# GregTrack_BIG_POW_v1_0.net
KiCad netlist of a schematic drawn in Altium Designer
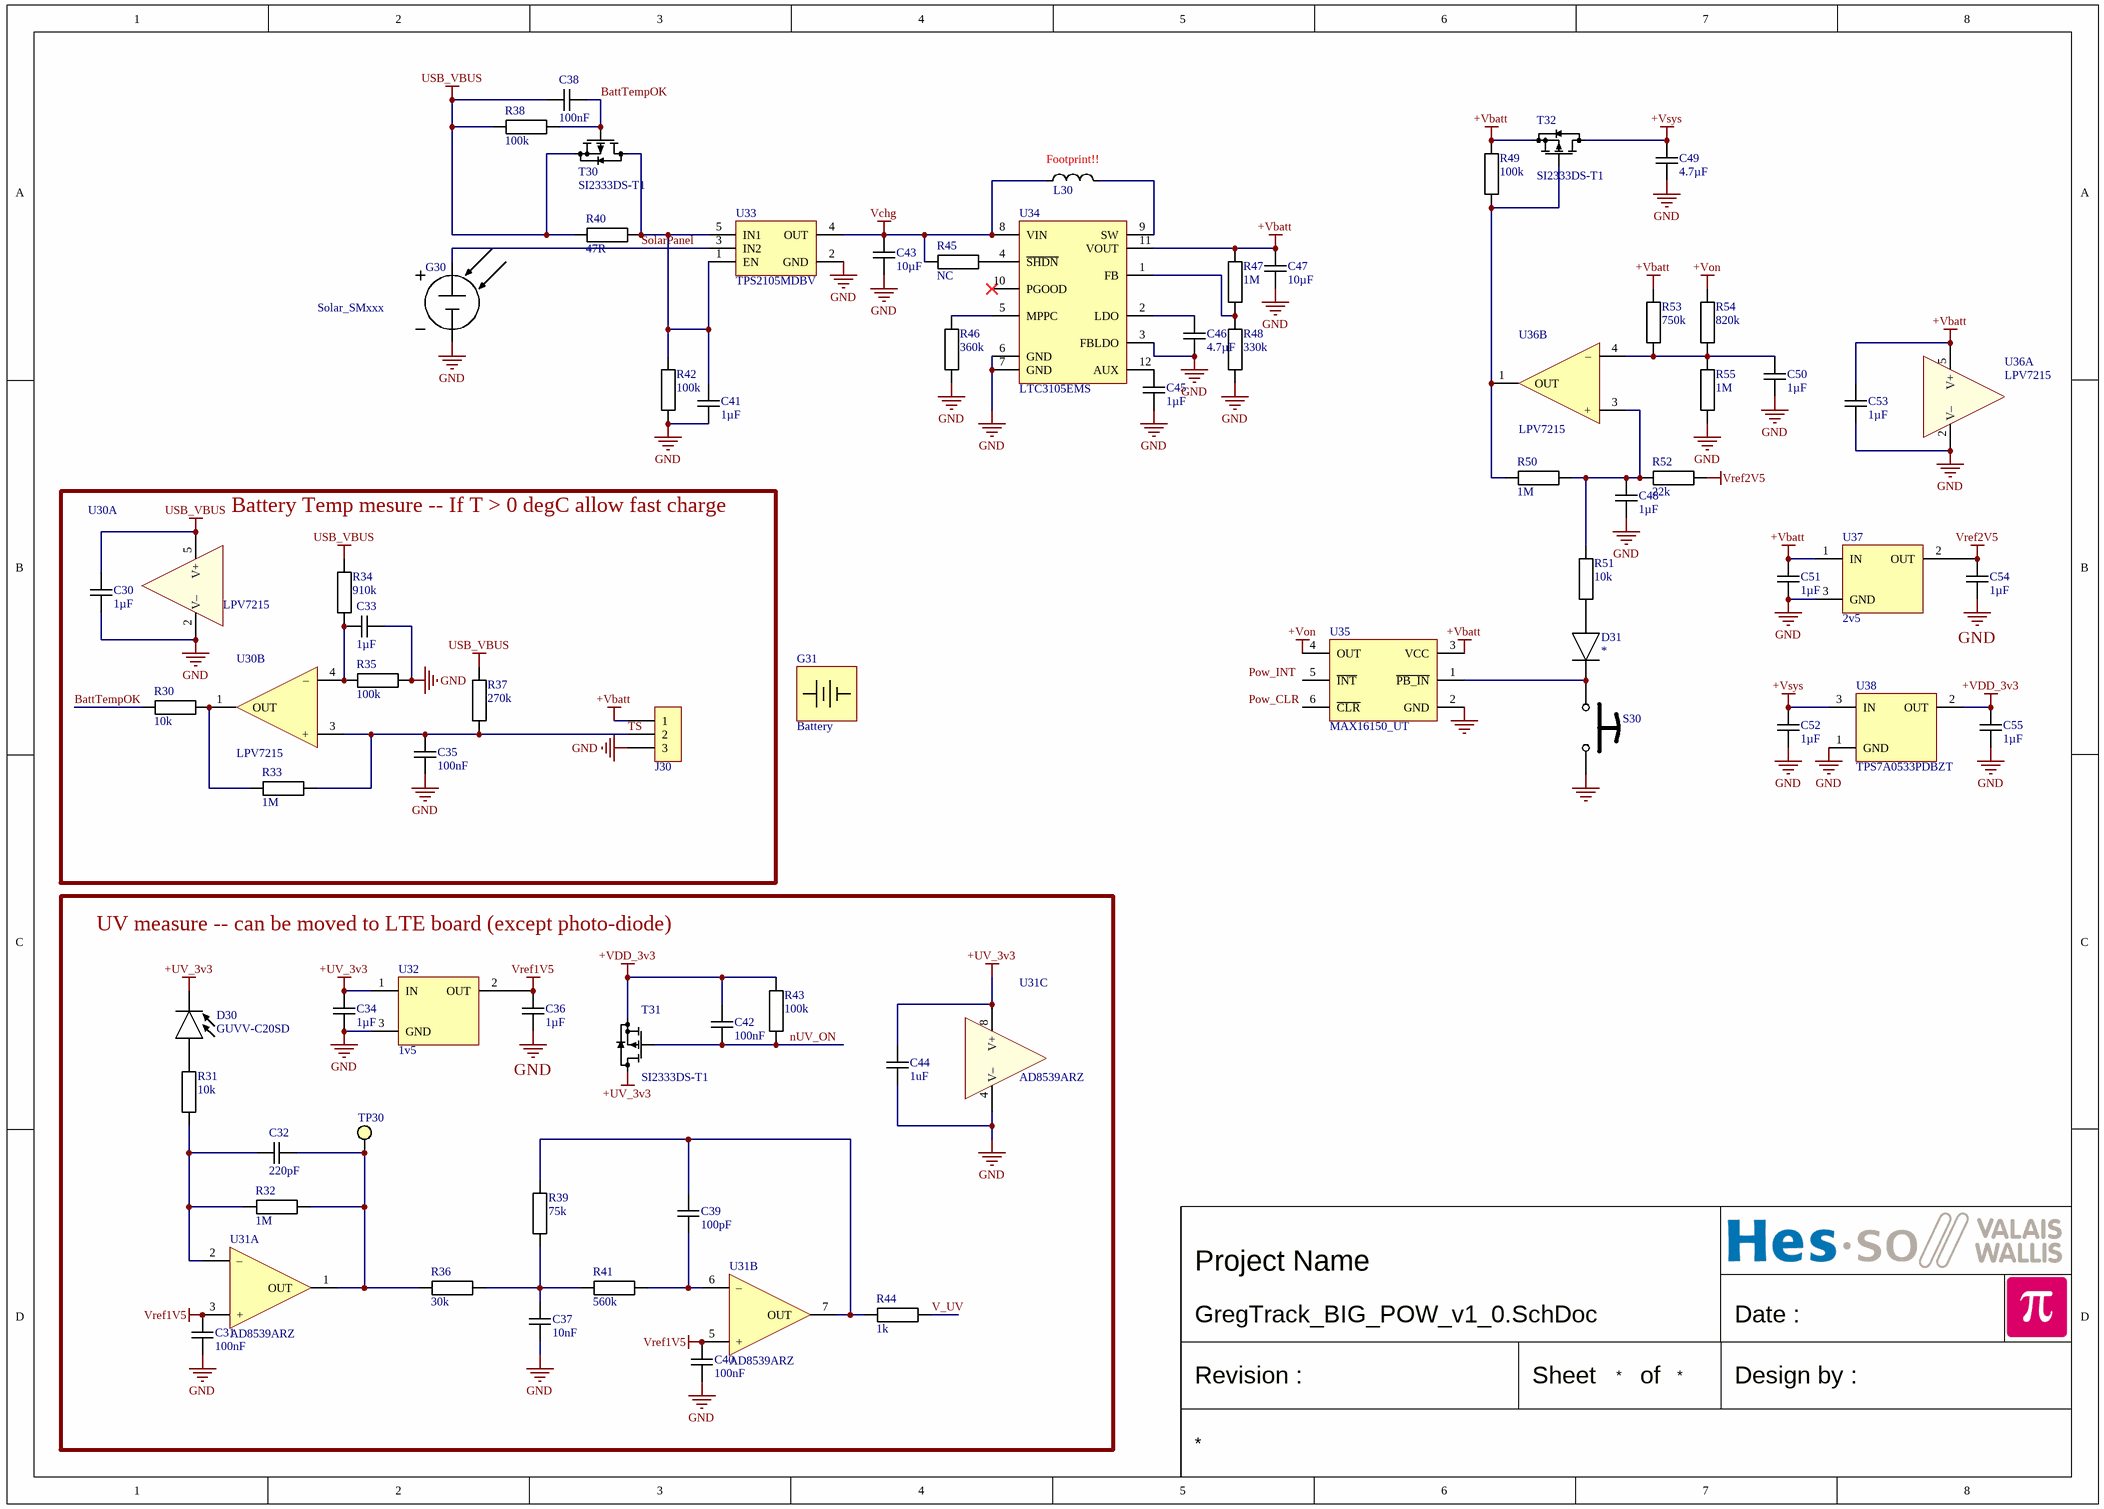
[diagram p0: GregTrack_BIG_POW_v1_0.SchDoc]

(export (version "E")
  (design (tool "Eeschema 10.0.6"))
  (components
    (comp (ref "C30")
      (value "1µF")
      (footprint "CAPACITOR 1005 REFLOW")
      (description "Capacitor 1005")
      (fields (field (name "TOLERANCE") "+/-20%") (field (name "VOLTAGE") "10V"))
      (libsource (lib "Capacitor") (part "Capacitor"))
    )
    (comp (ref "C31")
      (value "100nF")
      (footprint "CAPACITOR 1005 REFLOW")
      (description "Capacitor 1005")
      (fields (field (name "TOLERANCE") "+/-20%") (field (name "VOLTAGE") "10V"))
      (libsource (lib "Capacitor") (part "Capacitor"))
    )
    (comp (ref "C32")
      (value "220pF")
      (footprint "CAPACITOR 1005 REFLOW")
      (description "Capacitor 1005")
      (fields (field (name "TOLERANCE") "+/-5%") (field (name "VOLTAGE") "10V"))
      (libsource (lib "Capacitor") (part "Capacitor"))
    )
    (comp (ref "C33")
      (value "1µF")
      (footprint "CAPACITOR 1005 REFLOW")
      (description "Capacitor 1005")
      (fields (field (name "TOLERANCE") "+/-20%") (field (name "VOLTAGE") "10V"))
      (libsource (lib "Capacitor") (part "Capacitor"))
    )
    (comp (ref "C34")
      (value "1µF")
      (footprint "CAPACITOR 1005 REFLOW")
      (description "Capacitor 1005")
      (fields (field (name "TOLERANCE") "+/-20%") (field (name "VOLTAGE") "10V"))
      (libsource (lib "Capacitor") (part "Capacitor"))
    )
    (comp (ref "C35")
      (value "100nF")
      (footprint "CAPACITOR 1005 REFLOW")
      (description "Capacitor 1005")
      (fields (field (name "TOLERANCE") "+/-20%") (field (name "VOLTAGE") "10V"))
      (libsource (lib "Capacitor") (part "Capacitor"))
    )
    (comp (ref "C36")
      (value "1µF")
      (footprint "CAPACITOR 1005 REFLOW")
      (description "Capacitor 1005")
      (fields (field (name "TOLERANCE") "+/-20%") (field (name "VOLTAGE") "10V"))
      (libsource (lib "Capacitor") (part "Capacitor"))
    )
    (comp (ref "C37")
      (value "10nF")
      (footprint "CAPACITOR 1005 REFLOW")
      (description "Capacitor 1005")
      (fields (field (name "TOLERANCE") "+/-5%") (field (name "VOLTAGE") "10V"))
      (libsource (lib "Capacitor") (part "Capacitor"))
    )
    (comp (ref "C38")
      (value "100nF")
      (footprint "CAPACITOR 2012 REFLOW")
      (description "Capacitor 2012")
      (fields (field (name "TOLERANCE") "+/-20%") (field (name "VOLTAGE") "10V"))
      (libsource (lib "Capacitor") (part "Capacitor"))
    )
    (comp (ref "C39")
      (value "100pF")
      (footprint "CAPACITOR 1005 REFLOW")
      (description "Capacitor 1005")
      (fields (field (name "TOLERANCE") "+/-5%") (field (name "VOLTAGE") "10V"))
      (libsource (lib "Capacitor") (part "Capacitor"))
    )
    (comp (ref "C40")
      (value "100nF")
      (footprint "CAPACITOR 1005 REFLOW")
      (description "Capacitor 1005")
      (fields (field (name "TOLERANCE") "+/-20%") (field (name "VOLTAGE") "10V"))
      (libsource (lib "Capacitor") (part "Capacitor"))
    )
    (comp (ref "C41")
      (value "1µF")
      (footprint "CAPACITOR 2012 REFLOW")
      (description "Capacitor 2012")
      (fields (field (name "TOLERANCE") "+/-20%") (field (name "VOLTAGE") "10V"))
      (libsource (lib "Capacitor") (part "Capacitor"))
    )
    (comp (ref "C42")
      (value "100nF")
      (footprint "CAPACITOR 1005 REFLOW")
      (description "Capacitor 1005")
      (fields (field (name "TOLERANCE") "+/-20%") (field (name "VOLTAGE") "10V"))
      (libsource (lib "Capacitor") (part "Capacitor"))
    )
    (comp (ref "C43")
      (value "10µF")
      (footprint "CAPACITOR 2012 REFLOW")
      (description "Capacitor 2012")
      (fields (field (name "TOLERANCE") "+/-20%") (field (name "VOLTAGE") "10V"))
      (libsource (lib "Capacitor") (part "Capacitor"))
    )
    (comp (ref "C44")
      (value "1uF")
      (footprint "CAPACITOR 1005 REFLOW")
      (description "Capacitor 1005")
      (fields (field (name "TOLERANCE") "+/-20%") (field (name "VOLTAGE") "10V"))
      (libsource (lib "Capacitor") (part "Capacitor"))
    )
    (comp (ref "C45")
      (value "1µF")
      (footprint "CAPACITOR 1005 REFLOW")
      (description "Capacitor 1005")
      (fields (field (name "TOLERANCE") "+/-20%") (field (name "VOLTAGE") "10V"))
      (libsource (lib "Capacitor") (part "Capacitor"))
    )
    (comp (ref "C46")
      (value "4.7µF")
      (footprint "CAPACITOR 1005 REFLOW")
      (description "Capacitor 1005")
      (fields (field (name "TOLERANCE") "+/-20%") (field (name "VOLTAGE") "10V"))
      (libsource (lib "Capacitor") (part "Capacitor"))
    )
    (comp (ref "C47")
      (value "10µF")
      (footprint "CAPACITOR 2012 REFLOW")
      (description "Capacitor 2012")
      (fields (field (name "TOLERANCE") "+/-20%") (field (name "VOLTAGE") "10V"))
      (libsource (lib "Capacitor") (part "Capacitor"))
    )
    (comp (ref "C48")
      (value "1µF")
      (footprint "CAPACITOR 1005 REFLOW")
      (description "Capacitor 1005")
      (fields (field (name "TOLERANCE") "+/-20%") (field (name "VOLTAGE") "10V"))
      (libsource (lib "Capacitor") (part "Capacitor"))
    )
    (comp (ref "C49")
      (value "4.7µF")
      (footprint "CAPACITOR 1005 REFLOW")
      (description "Capacitor 1005")
      (fields (field (name "TOLERANCE") "+/-20%") (field (name "VOLTAGE") "10V"))
      (libsource (lib "Capacitor") (part "Capacitor"))
    )
    (comp (ref "C50")
      (value "1µF")
      (footprint "CAPACITOR 1005 REFLOW")
      (description "Capacitor 1005")
      (fields (field (name "TOLERANCE") "+/-20%") (field (name "VOLTAGE") "10V"))
      (libsource (lib "Capacitor") (part "Capacitor"))
    )
    (comp (ref "C51")
      (value "1µF")
      (footprint "CAPACITOR 1005 REFLOW")
      (description "Capacitor 1005")
      (fields (field (name "TOLERANCE") "+/-20%") (field (name "VOLTAGE") "10V"))
      (libsource (lib "Capacitor") (part "Capacitor"))
    )
    (comp (ref "C52")
      (value "1µF")
      (footprint "CAPACITOR 1005 REFLOW")
      (description "Capacitor 1005")
      (fields (field (name "TOLERANCE") "+/-20%") (field (name "VOLTAGE") "10V"))
      (libsource (lib "Capacitor") (part "Capacitor"))
    )
    (comp (ref "C53")
      (value "1µF")
      (footprint "CAPACITOR 1005 REFLOW")
      (description "Capacitor 1005")
      (fields (field (name "TOLERANCE") "+/-20%") (field (name "VOLTAGE") "10V"))
      (libsource (lib "Capacitor") (part "Capacitor"))
    )
    (comp (ref "C54")
      (value "1µF")
      (footprint "CAPACITOR 1005 REFLOW")
      (description "Capacitor 1005")
      (fields (field (name "TOLERANCE") "+/-20%") (field (name "VOLTAGE") "10V"))
      (libsource (lib "Capacitor") (part "Capacitor"))
    )
    (comp (ref "C55")
      (value "1µF")
      (footprint "CAPACITOR 1005 REFLOW")
      (description "Capacitor 1005")
      (fields (field (name "TOLERANCE") "+/-20%") (field (name "VOLTAGE") "10V"))
      (libsource (lib "Capacitor") (part "Capacitor"))
    )
    (comp (ref "D30")
      (value "GUVV-C20SD")
      (footprint "Photodiode Genuv GUV series")
      (description "Schottky Photodiode SMD 2.4x1.8mm")
      (libsource (lib "Diode") (part "Photodiode Genuv GUVV-C20SD"))
    )
    (comp (ref "D31")
      (value "*")
      (footprint "DIODE SOD923-F REFLOW")
      (description "Diode generic 2 leads")
      (libsource (lib "Diode") (part "DIODE"))
    )
    (comp (ref "G30")
      (value "Solar_SMxxx")
      (footprint "SOLAR_SM531K08TF")
      (libsource (lib "ECSlib") (part "Solar_SMxxx"))
    )
    (comp (ref "G31")
      (value "Battery")
      (footprint "Battery_ICP543759PMT")
      (description "ICP622540PMT")
      (libsource (lib "ECSlib") (part "Battery"))
    )
    (comp (ref "J30")
      (value "NC")
      (footprint "PinHeader1x3 P2.54 A SMD")
      (description "Plug connector")
      (libsource (lib "PinHeader") (part "PinHeader1x3"))
    )
    (comp (ref "L30")
      (value "10uH")
      (footprint "INDUCTOR 5750 REFLOW")
      (description "Inductor IHLP2020BZER100M51")
      (libsource (lib "Inductor") (part "Inductor"))
    )
    (comp (ref "R30")
      (value "10k")
      (footprint "RESISTOR 1005 REFLOW")
      (description "Resistor 1005")
      (fields (field (name "TOLERANCE") "1%"))
      (libsource (lib "Resistor") (part "Resistor"))
    )
    (comp (ref "R31")
      (value "10k")
      (footprint "RESISTOR 1005 REFLOW")
      (description "Resistor 1005")
      (fields (field (name "TOLERANCE") "1%"))
      (libsource (lib "Resistor") (part "Resistor"))
    )
    (comp (ref "R32")
      (value "1M")
      (footprint "RESISTOR 1005 REFLOW")
      (description "Resistor 1005")
      (fields (field (name "TOLERANCE") "1%"))
      (libsource (lib "Resistor") (part "Resistor"))
    )
    (comp (ref "R33")
      (value "1M")
      (footprint "RESISTOR 1005 REFLOW")
      (description "Resistor 1005")
      (fields (field (name "TOLERANCE") "1%"))
      (libsource (lib "Resistor") (part "Resistor"))
    )
    (comp (ref "R34")
      (value "910k")
      (footprint "RESISTOR 1005 REFLOW")
      (description "Resistor 1005")
      (fields (field (name "TOLERANCE") "1%"))
      (libsource (lib "Resistor") (part "Resistor"))
    )
    (comp (ref "R35")
      (value "100k")
      (footprint "RESISTOR 1005 REFLOW")
      (description "Resistor 1005")
      (fields (field (name "TOLERANCE") "1%"))
      (libsource (lib "Resistor") (part "Resistor"))
    )
    (comp (ref "R36")
      (value "30k")
      (footprint "RESISTOR 1005 REFLOW")
      (description "Resistor 1005")
      (fields (field (name "TOLERANCE") "1%"))
      (libsource (lib "Resistor") (part "Resistor"))
    )
    (comp (ref "R37")
      (value "270k")
      (footprint "RESISTOR 1005 REFLOW")
      (description "Resistor 1005")
      (fields (field (name "TOLERANCE") "1%"))
      (libsource (lib "Resistor") (part "Resistor"))
    )
    (comp (ref "R38")
      (value "100k")
      (footprint "RESISTOR 1005 REFLOW")
      (description "Resistor 1005")
      (fields (field (name "TOLERANCE") "1%"))
      (libsource (lib "Resistor") (part "Resistor"))
    )
    (comp (ref "R39")
      (value "75k")
      (footprint "RESISTOR 1005 REFLOW")
      (description "Resistor 1005")
      (fields (field (name "TOLERANCE") "1%"))
      (libsource (lib "Resistor") (part "Resistor"))
    )
    (comp (ref "R40")
      (value "47R")
      (footprint "RESISTOR 2012 REFLOW")
      (description "Resistor 2012, 1% 0.25W")
      (fields (field (name "TOLERANCE") "1%"))
      (libsource (lib "Resistor") (part "Resistor"))
    )
    (comp (ref "R41")
      (value "560k")
      (footprint "RESISTOR 1005 REFLOW")
      (description "Resistor 1005")
      (fields (field (name "TOLERANCE") "1%"))
      (libsource (lib "Resistor") (part "Resistor"))
    )
    (comp (ref "R42")
      (value "100k")
      (footprint "RESISTOR 1005 REFLOW")
      (description "Resistor 1005")
      (fields (field (name "TOLERANCE") "1%"))
      (libsource (lib "Resistor") (part "Resistor"))
    )
    (comp (ref "R43")
      (value "100k")
      (footprint "RESISTOR 1005 REFLOW")
      (description "Resistor 1005")
      (fields (field (name "TOLERANCE") "1%"))
      (libsource (lib "Resistor") (part "Resistor"))
    )
    (comp (ref "R44")
      (value "1k")
      (footprint "RESISTOR 1005 REFLOW")
      (description "Resistor 1005")
      (fields (field (name "TOLERANCE") "1%"))
      (libsource (lib "Resistor") (part "Resistor"))
    )
    (comp (ref "R45")
      (value "NC")
      (footprint "RESISTOR 1005 REFLOW")
      (description "Resistor 1005")
      (fields (field (name "TOLERANCE") "1%"))
      (libsource (lib "Resistor") (part "Resistor"))
    )
    (comp (ref "R46")
      (value "360k")
      (footprint "RESISTOR 1005 REFLOW")
      (description "Resistor 1005")
      (fields (field (name "TOLERANCE") "1%"))
      (libsource (lib "Resistor") (part "Resistor"))
    )
    (comp (ref "R47")
      (value "1M")
      (footprint "RESISTOR 1005 REFLOW")
      (description "Resistor 1005")
      (fields (field (name "TOLERANCE") "1%"))
      (libsource (lib "Resistor") (part "Resistor"))
    )
    (comp (ref "R48")
      (value "330k")
      (footprint "RESISTOR 1005 REFLOW")
      (description "Resistor 1005")
      (fields (field (name "TOLERANCE") "1%"))
      (libsource (lib "Resistor") (part "Resistor"))
    )
    (comp (ref "R49")
      (value "100k")
      (footprint "RESISTOR 1005 REFLOW")
      (description "Resistor 1005")
      (fields (field (name "TOLERANCE") "1%"))
      (libsource (lib "Resistor") (part "Resistor"))
    )
    (comp (ref "R50")
      (value "1M")
      (footprint "RESISTOR 1005 REFLOW")
      (description "Resistor 1005")
      (fields (field (name "TOLERANCE") "1%"))
      (libsource (lib "Resistor") (part "Resistor"))
    )
    (comp (ref "R51")
      (value "10k")
      (footprint "RESISTOR 1005 REFLOW")
      (description "Resistor 1005")
      (fields (field (name "TOLERANCE") "1%"))
      (libsource (lib "Resistor") (part "Resistor"))
    )
    (comp (ref "R52")
      (value "22k")
      (footprint "RESISTOR 1005 REFLOW")
      (description "Resistor 1005")
      (fields (field (name "TOLERANCE") "1%"))
      (libsource (lib "Resistor") (part "Resistor"))
    )
    (comp (ref "R53")
      (value "750k")
      (footprint "RESISTOR 1005 REFLOW")
      (description "Resistor 1005")
      (fields (field (name "TOLERANCE") "1%"))
      (libsource (lib "Resistor") (part "Resistor"))
    )
    (comp (ref "R54")
      (value "820k")
      (footprint "RESISTOR 1005 REFLOW")
      (description "Resistor 1005")
      (fields (field (name "TOLERANCE") "1%"))
      (libsource (lib "Resistor") (part "Resistor"))
    )
    (comp (ref "R55")
      (value "1M")
      (footprint "RESISTOR 1005 REFLOW")
      (description "Resistor 1005")
      (fields (field (name "TOLERANCE") "1%"))
      (libsource (lib "Resistor") (part "Resistor"))
    )
    (comp (ref "S30")
      (value "*")
      (footprint "Push Button C6.2x4.1 WE 434781025816")
      (description "Push Button, 2 pins")
      (libsource (lib "Button") (part "Push Button 2Pins"))
    )
    (comp (ref "T30")
      (value "SI2333DS-T1")
      (footprint "SOT23 P0.95 C1.6x3.0 H1.3")
      (description "Generic MOS-P")
      (libsource (lib "Transistor") (part "MOS-P SOT23 G-S-D"))
    )
    (comp (ref "T31")
      (value "SI2333DS-T1")
      (footprint "SOT23 P0.95 C1.6x3.0 H1.3")
      (description "Generic MOS-P")
      (libsource (lib "Transistor") (part "MOS-P SOT23 G-S-D"))
    )
    (comp (ref "T32")
      (value "SI2333DS-T1")
      (footprint "SOT23 P0.95 C1.6x3.0 H1.3")
      (description "Generic MOS-P")
      (libsource (lib "Transistor") (part "MOS-P SOT23 G-S-D"))
    )
    (comp (ref "TP30")
      (value "*")
      (footprint "Hole 0.25 D0.8")
      (description "Hole")
      (libsource (lib "Testpoint") (part "Hole"))
    )
    (comp (ref "U30")
      (value "LPV7215")
      (footprint "SOT23-5 P0.95 C1.6x3.0 H1.3")
      (description "Generic Single Comparator 5pins 1OUT/2-V/3+IN/4-IN/5+V")
      (libsource (lib "Amplifier") (part "COMPARATOR SINGLE SOT23-5"))
    )
    (comp (ref "U31")
      (value "AD8539ARZ")
      (footprint "SO8 P1.27 C4.0X5.0 H1.75")
      (description "Generic dual OPA 8 pins")
      (libsource (lib "Amplifier") (part "OPA DUAL"))
    )
    (comp (ref "U32")
      (value "1v5")
      (footprint "SOT23 P0.95 C1.6x3.0 H1.3")
      (description "ISL21080")
      (libsource (lib "Regulator") (part "REFERENCE SOT23 IN,OUT,GND"))
    )
    (comp (ref "U33")
      (value "TPS2105MDBV")
      (footprint "SOT23-5 P0.95 C1.6x3.0 H1.3")
      (description "Power-Distribution Switch")
      (libsource (lib "IntegratedCircuit") (part "TPS2105MDBV"))
    )
    (comp (ref "U34")
      (value "LTC3105EMS")
      (footprint "MSOP12 P0.65 C3.0X4.0 H0.9")
      (description "400mA Step-Up DC/DC Converter")
      (libsource (lib "VoltageConverter") (part "LTC3105EMS"))
    )
    (comp (ref "U35")
      (value "MAX16150_UT")
      (footprint "SOT23-6 P0.95 C1.5x3.0 H1.3")
      (description "nanoPower Pushbutton On/Off Controller and Battery Freshness Seal")
      (libsource (lib "IntegratedCircuit") (part "MAX16150_UT"))
    )
    (comp (ref "U36")
      (value "LPV7215")
      (footprint "SOT23-5 P0.95 C1.6x3.0 H1.3")
      (description "Generic Single Comparator 5pins 1OUT/2-V/3+IN/4-IN/5+V")
      (libsource (lib "Amplifier") (part "COMPARATOR SINGLE SOT23-5"))
    )
    (comp (ref "U37")
      (value "2v5")
      (footprint "SOT23 P0.95 C1.6x3.0 H1.3")
      (description "ISL21080")
      (libsource (lib "Regulator") (part "REFERENCE SOT23 IN,OUT,GND"))
    )
    (comp (ref "U38")
      (value "TPS7A0533PDBZT")
      (footprint "SOT23 P0.95 C1.6x3.0 H1.3")
      (description "Generic Positive Voltage Regulator")
      (libsource (lib "Regulator") (part "REGPOS SOT23 GND,OUT,IN"))
    )
  )
  (nets
    (net (code "1") (name "+UV_3v3") (class "Default")
      (node (ref "C34") (pin "2") (pinfunction "2_2") (pintype "passive"))
      (node (ref "C44") (pin "2") (pinfunction "2_2") (pintype "passive"))
      (node (ref "D30") (pin "1") (pinfunction "C_1") (pintype "passive"))
      (node (ref "T31") (pin "3") (pinfunction "D_3") (pintype "passive"))
      (node (ref "U31") (pin "8") (pinfunction "V+_8") (pintype "passive"))
      (node (ref "U32") (pin "1") (pinfunction "IN_1") (pintype "passive"))
    )
    (net (code "2") (name "+VDD_3v3") (class "Default")
      (node (ref "C42") (pin "1") (pinfunction "1_1") (pintype "passive"))
      (node (ref "C55") (pin "2") (pinfunction "2_2") (pintype "passive"))
      (node (ref "R43") (pin "2") (pinfunction "2_2") (pintype "passive"))
      (node (ref "T31") (pin "2") (pinfunction "S_2") (pintype "passive"))
      (node (ref "U38") (pin "2") (pinfunction "OUT_2") (pintype "passive"))
    )
    (net (code "3") (name "+Vbatt") (class "Default")
      (node (ref "C47") (pin "2") (pinfunction "2_2") (pintype "passive"))
      (node (ref "C51") (pin "2") (pinfunction "2_2") (pintype "passive"))
      (node (ref "C53") (pin "2") (pinfunction "2_2") (pintype "passive"))
      (node (ref "J30") (pin "1") (pinfunction "1_1") (pintype "passive"))
      (node (ref "R47") (pin "1") (pinfunction "1_1") (pintype "passive"))
      (node (ref "R49") (pin "2") (pinfunction "2_2") (pintype "passive"))
      (node (ref "R53") (pin "2") (pinfunction "2_2") (pintype "passive"))
      (node (ref "T32") (pin "2") (pinfunction "S_2") (pintype "passive"))
      (node (ref "U34") (pin "11") (pinfunction "VOUT_11") (pintype "passive"))
      (node (ref "U35") (pin "3") (pinfunction "VCC_3") (pintype "passive"))
      (node (ref "U36") (pin "5") (pinfunction "V+_5") (pintype "passive"))
      (node (ref "U37") (pin "1") (pinfunction "IN_1") (pintype "passive"))
    )
    (net (code "4") (name "+Von") (class "Default")
      (node (ref "R54") (pin "2") (pinfunction "2_2") (pintype "passive"))
      (node (ref "U35") (pin "4") (pinfunction "OUT_4") (pintype "passive"))
    )
    (net (code "5") (name "+Vsys") (class "Default")
      (node (ref "C49") (pin "2") (pinfunction "2_2") (pintype "passive"))
      (node (ref "C52") (pin "2") (pinfunction "2_2") (pintype "passive"))
      (node (ref "T32") (pin "3") (pinfunction "D_3") (pintype "passive"))
      (node (ref "U38") (pin "3") (pinfunction "IN_3") (pintype "passive"))
    )
    (net (code "6") (name "/BattTempOK") (class "Default")
      (node (ref "C38") (pin "1") (pinfunction "1_1") (pintype "passive"))
      (node (ref "R30") (pin "2") (pinfunction "2_2") (pintype "passive"))
      (node (ref "R38") (pin "2") (pinfunction "2_2") (pintype "passive"))
      (node (ref "T30") (pin "1") (pinfunction "G_1") (pintype "passive"))
    )
    (net (code "9") (name "/SolarPanel") (class "Default")
      (node (ref "G30") (pin "1") (pinfunction "+_1") (pintype "passive"))
      (node (ref "U33") (pin "3") (pinfunction "IN2_3") (pintype "passive"))
    )
    (net (code "10") (name "/TS") (class "Default")
      (node (ref "C35") (pin "1") (pinfunction "1_1") (pintype "passive"))
      (node (ref "J30") (pin "2") (pinfunction "2_2") (pintype "passive"))
      (node (ref "R33") (pin "1") (pinfunction "1_1") (pintype "passive"))
      (node (ref "R37") (pin "1") (pinfunction "1_1") (pintype "passive"))
      (node (ref "U30") (pin "3") (pinfunction "+_3") (pintype "passive"))
    )
    (net (code "11") (name "/V_UV") (class "Default")
      (node (ref "R44") (pin "1") (pinfunction "1_1") (pintype "passive"))
    )
    (net (code "12") (name "/nUV_ON") (class "Default")
      (node (ref "C42") (pin "2") (pinfunction "2_2") (pintype "passive"))
      (node (ref "R43") (pin "1") (pinfunction "1_1") (pintype "passive"))
      (node (ref "T31") (pin "1") (pinfunction "G_1") (pintype "passive"))
    )
    (net (code "13") (name "GND") (class "Default")
      (node (ref "C30") (pin "1") (pinfunction "1_1") (pintype "passive"))
      (node (ref "C31") (pin "1") (pinfunction "1_1") (pintype "passive"))
      (node (ref "C33") (pin "1") (pinfunction "1_1") (pintype "passive"))
      (node (ref "C34") (pin "1") (pinfunction "1_1") (pintype "passive"))
      (node (ref "C35") (pin "2") (pinfunction "2_2") (pintype "passive"))
      (node (ref "C36") (pin "1") (pinfunction "1_1") (pintype "passive"))
      (node (ref "C37") (pin "1") (pinfunction "1_1") (pintype "passive"))
      (node (ref "C40") (pin "1") (pinfunction "1_1") (pintype "passive"))
      (node (ref "C41") (pin "1") (pinfunction "1_1") (pintype "passive"))
      (node (ref "C43") (pin "1") (pinfunction "1_1") (pintype "passive"))
      (node (ref "C44") (pin "1") (pinfunction "1_1") (pintype "passive"))
      (node (ref "C45") (pin "1") (pinfunction "1_1") (pintype "passive"))
      (node (ref "C46") (pin "1") (pinfunction "1_1") (pintype "passive"))
      (node (ref "C47") (pin "1") (pinfunction "1_1") (pintype "passive"))
      (node (ref "C48") (pin "1") (pinfunction "1_1") (pintype "passive"))
      (node (ref "C49") (pin "1") (pinfunction "1_1") (pintype "passive"))
      (node (ref "C50") (pin "1") (pinfunction "1_1") (pintype "passive"))
      (node (ref "C51") (pin "1") (pinfunction "1_1") (pintype "passive"))
      (node (ref "C52") (pin "1") (pinfunction "1_1") (pintype "passive"))
      (node (ref "C53") (pin "1") (pinfunction "1_1") (pintype "passive"))
      (node (ref "C54") (pin "1") (pinfunction "1_1") (pintype "passive"))
      (node (ref "C55") (pin "1") (pinfunction "1_1") (pintype "passive"))
      (node (ref "G30") (pin "2") (pinfunction "-_2") (pintype "passive"))
      (node (ref "J30") (pin "3") (pinfunction "3_3") (pintype "passive"))
      (node (ref "R35") (pin "1") (pinfunction "1_1") (pintype "passive"))
      (node (ref "R42") (pin "2") (pinfunction "2_2") (pintype "passive"))
      (node (ref "R46") (pin "2") (pinfunction "2_2") (pintype "passive"))
      (node (ref "R48") (pin "2") (pinfunction "2_2") (pintype "passive"))
      (node (ref "R55") (pin "1") (pinfunction "1_1") (pintype "passive"))
      (node (ref "S30") (pin "2") (pinfunction "2_2") (pintype "passive"))
      (node (ref "U30") (pin "2") (pinfunction "V–_2") (pintype "passive"))
      (node (ref "U31") (pin "4") (pinfunction "V–_4") (pintype "passive"))
      (node (ref "U32") (pin "3") (pinfunction "GND_3") (pintype "passive"))
      (node (ref "U33") (pin "2") (pinfunction "GND_2") (pintype "passive"))
      (node (ref "U34") (pin "3") (pinfunction "FBLDO_3") (pintype "passive"))
      (node (ref "U34") (pin "6") (pinfunction "GND_6") (pintype "passive"))
      (node (ref "U34") (pin "7") (pinfunction "GND_7") (pintype "passive"))
      (node (ref "U35") (pin "2") (pinfunction "GND_2") (pintype "passive"))
      (node (ref "U36") (pin "2") (pinfunction "V–_2") (pintype "passive"))
      (node (ref "U37") (pin "3") (pinfunction "GND_3") (pintype "passive"))
      (node (ref "U38") (pin "1") (pinfunction "GND_1") (pintype "passive"))
    )
    (net (code "14") (name "Net-(C37-Pad2)") (class "Default")
      (node (ref "C37") (pin "2") (pinfunction "2_2") (pintype "passive"))
      (node (ref "R36") (pin "1") (pinfunction "1_1") (pintype "passive"))
      (node (ref "R39") (pin "1") (pinfunction "1_1") (pintype "passive"))
      (node (ref "R41") (pin "2") (pinfunction "2_2") (pintype "passive"))
    )
    (net (code "15") (name "Net-(D30-A)") (class "Default")
      (node (ref "D30") (pin "2") (pinfunction "A_2") (pintype "passive"))
      (node (ref "R31") (pin "2") (pinfunction "2_2") (pintype "passive"))
    )
    (net (code "16") (name "Net-(D31-A)") (class "Default")
      (node (ref "D31") (pin "2") (pinfunction "A_2") (pintype "passive"))
      (node (ref "R51") (pin "2") (pinfunction "2_2") (pintype "passive"))
    )
    (net (code "17") (name "Net-(D31-C)") (class "Default")
      (node (ref "D31") (pin "1") (pinfunction "C_1") (pintype "passive"))
      (node (ref "S30") (pin "1") (pinfunction "1_1") (pintype "passive"))
      (node (ref "U35") (pin "1") (pinfunction "~{PB_IN}_1") (pintype "passive"))
    )
    (net (code "18") (name "Net-(T30-D)") (class "Default")
      (node (ref "C41") (pin "2") (pinfunction "2_2") (pintype "passive"))
      (node (ref "R40") (pin "2") (pinfunction "2_2") (pintype "passive"))
      (node (ref "R42") (pin "1") (pinfunction "1_1") (pintype "passive"))
      (node (ref "T30") (pin "3") (pinfunction "D_3") (pintype "passive"))
      (node (ref "U33") (pin "1") (pinfunction "EN_1") (pintype "passive"))
      (node (ref "U33") (pin "5") (pinfunction "IN1_5") (pintype "passive"))
    )
    (net (code "19") (name "Net-(T32-G)") (class "Default")
      (node (ref "R49") (pin "1") (pinfunction "1_1") (pintype "passive"))
      (node (ref "R50") (pin "1") (pinfunction "1_1") (pintype "passive"))
      (node (ref "T32") (pin "1") (pinfunction "G_1") (pintype "passive"))
      (node (ref "U36") (pin "1") (pinfunction "OUT_1") (pintype "passive"))
    )
    (net (code "20") (name "Net-(U30B-OUT)") (class "Default")
      (node (ref "R30") (pin "1") (pinfunction "1_1") (pintype "passive"))
      (node (ref "R33") (pin "2") (pinfunction "2_2") (pintype "passive"))
      (node (ref "U30") (pin "1") (pinfunction "OUT_1") (pintype "passive"))
    )
    (net (code "21") (name "Net-(U30B-–)") (class "Default")
      (node (ref "C33") (pin "2") (pinfunction "2_2") (pintype "passive"))
      (node (ref "R34") (pin "2") (pinfunction "2_2") (pintype "passive"))
      (node (ref "R35") (pin "2") (pinfunction "2_2") (pintype "passive"))
      (node (ref "U30") (pin "4") (pinfunction "–_4") (pintype "passive"))
    )
    (net (code "22") (name "Net-(U31A-OUT)") (class "Default")
      (node (ref "C32") (pin "2") (pinfunction "2_2") (pintype "passive"))
      (node (ref "R32") (pin "1") (pinfunction "1_1") (pintype "passive"))
      (node (ref "R36") (pin "2") (pinfunction "2_2") (pintype "passive"))
      (node (ref "TP30") (pin "1") (pinfunction "1_1") (pintype "passive"))
      (node (ref "U31") (pin "1") (pinfunction "OUT_1") (pintype "passive"))
    )
    (net (code "23") (name "Net-(U31A-–)") (class "Default")
      (node (ref "C32") (pin "1") (pinfunction "1_1") (pintype "passive"))
      (node (ref "R31") (pin "1") (pinfunction "1_1") (pintype "passive"))
      (node (ref "R32") (pin "2") (pinfunction "2_2") (pintype "passive"))
      (node (ref "U31") (pin "2") (pinfunction "–_2") (pintype "passive"))
    )
    (net (code "24") (name "Net-(U31B-OUT)") (class "Default")
      (node (ref "C39") (pin "2") (pinfunction "2_2") (pintype "passive"))
      (node (ref "R39") (pin "2") (pinfunction "2_2") (pintype "passive"))
      (node (ref "R44") (pin "2") (pinfunction "2_2") (pintype "passive"))
      (node (ref "U31") (pin "7") (pinfunction "OUT_7") (pintype "passive"))
    )
    (net (code "25") (name "Net-(U31B-–)") (class "Default")
      (node (ref "C39") (pin "1") (pinfunction "1_1") (pintype "passive"))
      (node (ref "R41") (pin "1") (pinfunction "1_1") (pintype "passive"))
      (node (ref "U31") (pin "6") (pinfunction "–_6") (pintype "passive"))
    )
    (net (code "26") (name "Net-(U34-AUX)") (class "Default")
      (node (ref "C45") (pin "2") (pinfunction "2_2") (pintype "passive"))
      (node (ref "U34") (pin "12") (pinfunction "AUX_12") (pintype "passive"))
    )
    (net (code "27") (name "Net-(U34-FB)") (class "Default")
      (node (ref "R47") (pin "2") (pinfunction "2_2") (pintype "passive"))
      (node (ref "R48") (pin "1") (pinfunction "1_1") (pintype "passive"))
      (node (ref "U34") (pin "1") (pinfunction "FB_1") (pintype "passive"))
    )
    (net (code "28") (name "Net-(U34-LDO)") (class "Default")
      (node (ref "C46") (pin "2") (pinfunction "2_2") (pintype "passive"))
      (node (ref "U34") (pin "2") (pinfunction "LDO_2") (pintype "passive"))
    )
    (net (code "29") (name "Net-(U34-MPPC)") (class "Default")
      (node (ref "R46") (pin "1") (pinfunction "1_1") (pintype "passive"))
      (node (ref "U34") (pin "5") (pinfunction "MPPC_5") (pintype "passive"))
    )
    (net (code "30") (name "Net-(U34-SW)") (class "Default")
      (node (ref "L30") (pin "2") (pinfunction "2_2") (pintype "passive"))
      (node (ref "U34") (pin "9") (pinfunction "SW_9") (pintype "passive"))
    )
    (net (code "31") (name "Net-(U34-~{SHDN})") (class "Default")
      (node (ref "R45") (pin "2") (pinfunction "2_2") (pintype "passive"))
      (node (ref "U34") (pin "4") (pinfunction "~{SHDN}_4") (pintype "passive"))
    )
    (net (code "32") (name "Net-(U36B-+)") (class "Default")
      (node (ref "C48") (pin "2") (pinfunction "2_2") (pintype "passive"))
      (node (ref "R50") (pin "2") (pinfunction "2_2") (pintype "passive"))
      (node (ref "R51") (pin "1") (pinfunction "1_1") (pintype "passive"))
      (node (ref "R52") (pin "1") (pinfunction "1_1") (pintype "passive"))
      (node (ref "U36") (pin "3") (pinfunction "+_3") (pintype "passive"))
    )
    (net (code "33") (name "Net-(U36B-–)") (class "Default")
      (node (ref "C50") (pin "2") (pinfunction "2_2") (pintype "passive"))
      (node (ref "R53") (pin "1") (pinfunction "1_1") (pintype "passive"))
      (node (ref "R54") (pin "1") (pinfunction "1_1") (pintype "passive"))
      (node (ref "R55") (pin "2") (pinfunction "2_2") (pintype "passive"))
      (node (ref "U36") (pin "4") (pinfunction "–_4") (pintype "passive"))
    )
    (net (code "34") (name "USB_VBUS") (class "Default")
      (node (ref "C30") (pin "2") (pinfunction "2_2") (pintype "passive"))
      (node (ref "C38") (pin "2") (pinfunction "2_2") (pintype "passive"))
      (node (ref "R34") (pin "1") (pinfunction "1_1") (pintype "passive"))
      (node (ref "R37") (pin "2") (pinfunction "2_2") (pintype "passive"))
      (node (ref "R38") (pin "1") (pinfunction "1_1") (pintype "passive"))
      (node (ref "R40") (pin "1") (pinfunction "1_1") (pintype "passive"))
      (node (ref "T30") (pin "2") (pinfunction "S_2") (pintype "passive"))
      (node (ref "U30") (pin "5") (pinfunction "V+_5") (pintype "passive"))
    )
    (net (code "35") (name "Vchg") (class "Default")
      (node (ref "C43") (pin "2") (pinfunction "2_2") (pintype "passive"))
      (node (ref "L30") (pin "1") (pinfunction "1_1") (pintype "passive"))
      (node (ref "R45") (pin "1") (pinfunction "1_1") (pintype "passive"))
      (node (ref "U33") (pin "4") (pinfunction "OUT_4") (pintype "passive"))
      (node (ref "U34") (pin "8") (pinfunction "VIN_8") (pintype "passive"))
    )
    (net (code "36") (name "Vref1V5") (class "Default")
      (node (ref "C31") (pin "2") (pinfunction "2_2") (pintype "passive"))
      (node (ref "C36") (pin "2") (pinfunction "2_2") (pintype "passive"))
      (node (ref "C40") (pin "2") (pinfunction "2_2") (pintype "passive"))
      (node (ref "U31") (pin "3") (pinfunction "+_3") (pintype "passive"))
      (node (ref "U31") (pin "5") (pinfunction "+_5") (pintype "passive"))
      (node (ref "U32") (pin "2") (pinfunction "OUT_2") (pintype "passive"))
    )
    (net (code "37") (name "Vref2V5") (class "Default")
      (node (ref "C54") (pin "2") (pinfunction "2_2") (pintype "passive"))
      (node (ref "R52") (pin "2") (pinfunction "2_2") (pintype "passive"))
      (node (ref "U37") (pin "2") (pinfunction "OUT_2") (pintype "passive"))
    )
    (net (code "38") (name "unconnected-(U34-PGOOD-Pad10)") (class "Default")
      (node (ref "U34") (pin "10") (pinfunction "PGOOD_10") (pintype "passive+no_connect"))
    )
    (net (code "39") (name "unconnected-(U35-~{CLR}-Pad6)") (class "Default")
      (node (ref "U35") (pin "6") (pinfunction "~{CLR}_6") (pintype "passive"))
    )
    (net (code "40") (name "unconnected-(U35-~{INT}-Pad5)") (class "Default")
      (node (ref "U35") (pin "5") (pinfunction "~{INT}_5") (pintype "passive"))
    )
  )
)
